# LED_Driver.net
KiCad netlist of a schematic drawn in Altium Designer
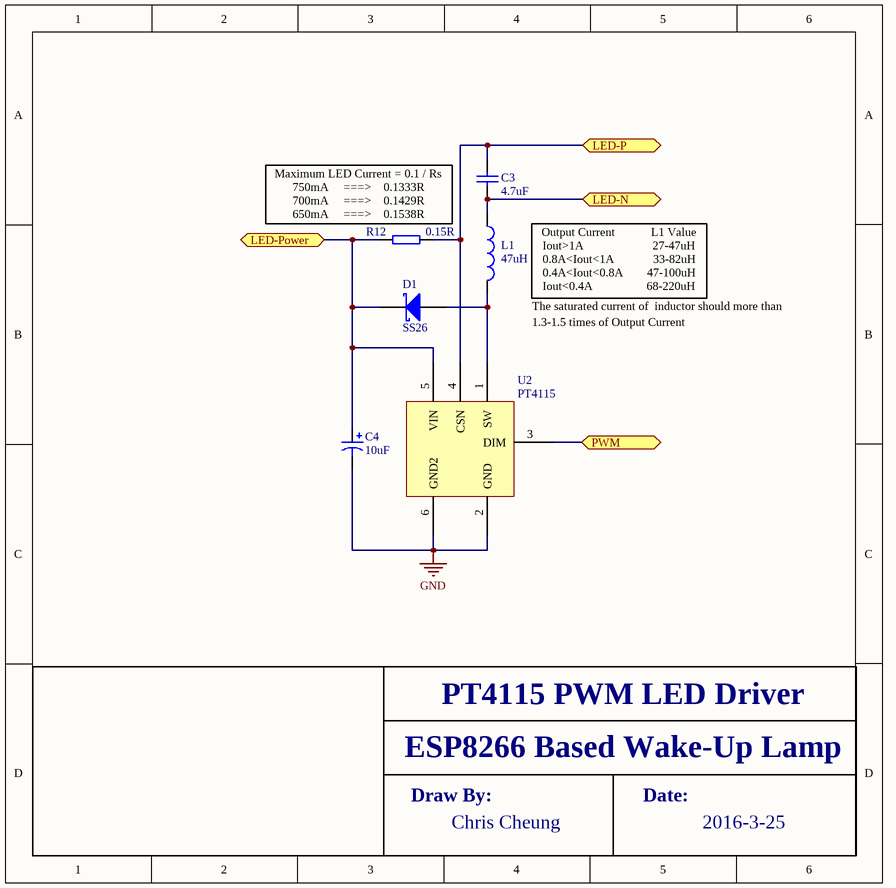
[diagram p0: LED Driver.SchDoc]

(export (version "E")
  (design (tool "Eeschema 10.0.6"))
  (components
    (comp (ref "C3")
      (value "4.7uF")
      (footprint "RAD-0.3")
      (description "Capacitor")
      (fields (field (name "Comment") "Cap") (field (name "PUBLISHER") "Altium Limited"))
      (libsource (lib "Miscellaneous Devices") (part "Cap"))
    )
    (comp (ref "C4")
      (value "10uF")
      (footprint "C0805")
      (description "Polarized Capacitor (Surface Mount)")
      (fields (field (name "Comment") "Cap Pol3") (field (name "PUBLISHER") "Altium Limited"))
      (libsource (lib "Miscellaneous Devices") (part "Cap Pol3"))
    )
    (comp (ref "D1")
      (value "SS26")
      (footprint "DO-204AL")
      (description "Schottky Rectifier")
      (fields (field (name "PUBLISHER") "Altium Limited"))
      (libsource (lib "Miscellaneous Devices") (part "Diode 11DQ03"))
    )
    (comp (ref "L1")
      (value "47uH")
      (footprint "0402-A")
      (description "Inductor")
      (fields (field (name "PUBLISHER") "Altium Limited"))
      (libsource (lib "Miscellaneous Devices") (part "Inductor"))
    )
    (comp (ref "R12")
      (value "0.15R")
      (footprint "SMT_R_0402")
      (description "Surface mount resistor 0402")
      (libsource (lib "Vowstar_Basic_Device") (part "SMT_R_0402"))
    )
    (comp (ref "U2") (value "PT4115") (description "LED Driver") (libsource (lib "Schlib1") (part "PT4115")))
  )
  (nets
    (net (code "1") (name "/LED-N") (class "Default")
      (node (ref "C3") (pin "1") (pinfunction "1_1") (pintype "passive"))
      (node (ref "L1") (pin "1") (pinfunction "1_1") (pintype "passive"))
    )
    (net (code "2") (name "/LED-P") (class "Default")
      (node (ref "C3") (pin "2") (pinfunction "2_2") (pintype "passive"))
      (node (ref "R12") (pin "2") (pinfunction "2_2") (pintype "passive"))
      (node (ref "U2") (pin "4") (pinfunction "CSN_4") (pintype "passive"))
    )
    (net (code "3") (name "/LED-Power") (class "Default")
      (node (ref "C4") (pin "1") (pinfunction "1_1") (pintype "passive"))
      (node (ref "D1") (pin "2") (pinfunction "K_2") (pintype "passive"))
      (node (ref "R12") (pin "1") (pinfunction "1_1") (pintype "passive"))
      (node (ref "U2") (pin "5") (pinfunction "VIN_5") (pintype "passive"))
    )
    (net (code "4") (name "/PWM") (class "Default")
      (node (ref "U2") (pin "3") (pinfunction "DIM_3") (pintype "passive"))
    )
    (net (code "5") (name "GND") (class "Default")
      (node (ref "C4") (pin "2") (pinfunction "2_2") (pintype "passive"))
      (node (ref "U2") (pin "2") (pinfunction "GND_2") (pintype "power_in"))
      (node (ref "U2") (pin "6") (pinfunction "GND2_6") (pintype "power_in"))
    )
    (net (code "6") (name "Net-(D1-A)") (class "Default")
      (node (ref "D1") (pin "1") (pinfunction "A_1") (pintype "passive"))
      (node (ref "L1") (pin "2") (pinfunction "2_2") (pintype "passive"))
      (node (ref "U2") (pin "1") (pinfunction "SW_1") (pintype "passive"))
    )
  )
)
